# vaja_1.net
KiCad netlist of a schematic drawn in Altium Designer
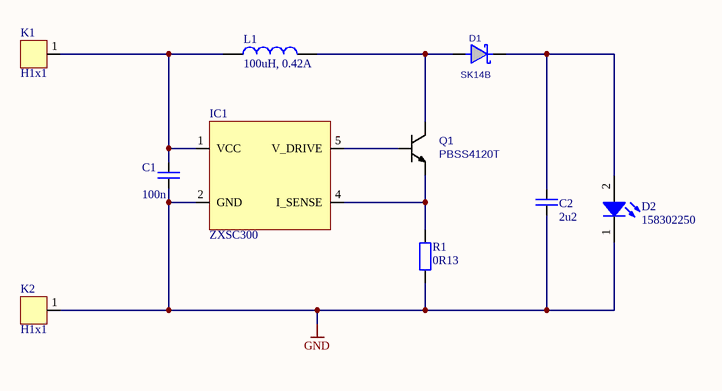
[diagram p0: vaja_1.SchDoc]

(export (version "E")
  (design (tool "Eeschema 10.0.6"))
  (components
    (comp (ref "C1")
      (value "100n")
      (footprint "C2012_0805I_M")
      (description "Capacitor")
      (libsource (lib "General") (part "C"))
    )
    (comp (ref "C2")
      (value "2u2")
      (footprint "C2012_0805I_M")
      (description "Capacitor")
      (libsource (lib "General") (part "C"))
    )
    (comp (ref "D1")
      (value "SK14B")
      (footprint "DO-214AA_SMB_L")
      (description "Schottky")
      (libsource (lib "vaja_1_lib") (part "SK14B"))
    )
    (comp (ref "D2")
      (value "158302250")
      (footprint "WL-SWTP_3022")
      (description "WL-SWTP SMT White Top view PLCC, size 3022, Daylight, 3.2V, 120deg")
      (fields (field (name "MANUFACTURER") "Wurth Elektronik"))
      (libsource (lib "WL-SWTP (rev21a) (1)") (part "158302250"))
    )
    (comp (ref "IC1")
      (value "ZXSC300")
      (footprint "SOT23-5")
      (description "Led driver IC")
      (libsource (lib "vaja_1_lib") (part "ZXSC300"))
    )
    (comp (ref "K1")
      (value "H1x1")
      (footprint "H1x1")
      (description "Header 1x1 (male)")
      (libsource (lib "Kon_Tipk") (part "H1x1"))
    )
    (comp (ref "K2")
      (value "H1x1")
      (footprint "H1x1")
      (description "Header 1x1 (male)")
      (libsource (lib "Kon_Tipk") (part "H1x1"))
    )
    (comp (ref "L1")
      (value "100uH, 0.42A")
      (footprint "WE-LQFS_4818")
      (description "WE-LQFS SMT Power Inductor, size 4818, 100uH, 0.42A")
      (fields
        (field (name "MANUFACTURER") "Wurth Elektronik")
        (field (name "MANUFACTURER PART NUMBER") "74406042101")
      )
      (libsource (lib "Altium_WE-LQFS (rev20a) (1)") (part "74406042101"))
    )
    (comp (ref "Q1")
      (value "PBSS4120T")
      (footprint "SOT23-3_L")
      (description "BC817")
      (libsource (lib "NPN") (part "BC817"))
    )
    (comp (ref "R1")
      (value "0R13")
      (footprint "R2012_0805I_M")
      (description "R")
      (libsource (lib "General") (part "R"))
    )
  )
  (nets
    (net (code "1") (name "GND") (class "Default")
      (node (ref "C1") (pin "2") (pinfunction "2_2") (pintype "passive"))
      (node (ref "C2") (pin "2") (pinfunction "2_2") (pintype "passive"))
      (node (ref "D2") (pin "1") (pinfunction "K_1") (pintype "passive"))
      (node (ref "IC1") (pin "2") (pinfunction "GND_2") (pintype "passive"))
      (node (ref "K2") (pin "1") (pinfunction "1_1") (pintype "passive"))
      (node (ref "R1") (pin "2") (pintype "passive"))
    )
    (net (code "2") (name "Net-(D1-A)") (class "Default")
      (node (ref "D1") (pin "2") (pinfunction "A_2") (pintype "passive"))
      (node (ref "L1") (pin "2") (pinfunction "2_2") (pintype "passive"))
      (node (ref "Q1") (pin "C") (pinfunction "C_C") (pintype "passive"))
    )
    (net (code "3") (name "Net-(D1-K)") (class "Default")
      (node (ref "C2") (pin "1") (pinfunction "1_1") (pintype "passive"))
      (node (ref "D1") (pin "1") (pinfunction "K_1") (pintype "passive"))
      (node (ref "D2") (pin "2") (pinfunction "A_2") (pintype "passive"))
    )
    (net (code "4") (name "Net-(IC1-I_SENSE)") (class "Default")
      (node (ref "IC1") (pin "4") (pinfunction "I_SENSE_4") (pintype "passive"))
      (node (ref "Q1") (pin "E") (pinfunction "E_E") (pintype "passive"))
      (node (ref "R1") (pin "1") (pintype "passive"))
    )
    (net (code "5") (name "Net-(IC1-VCC)") (class "Default")
      (node (ref "C1") (pin "1") (pinfunction "1_1") (pintype "passive"))
      (node (ref "IC1") (pin "1") (pinfunction "VCC_1") (pintype "passive"))
      (node (ref "K1") (pin "1") (pinfunction "1_1") (pintype "passive"))
      (node (ref "L1") (pin "1") (pinfunction "1_1") (pintype "passive"))
    )
    (net (code "6") (name "Net-(IC1-V_DRIVE)") (class "Default")
      (node (ref "IC1") (pin "5") (pinfunction "V_DRIVE_5") (pintype "passive"))
      (node (ref "Q1") (pin "B") (pinfunction "B_B") (pintype "passive"))
    )
  )
)
